# shieldv1_0.net
KiCad netlist of a schematic drawn in EAGLE
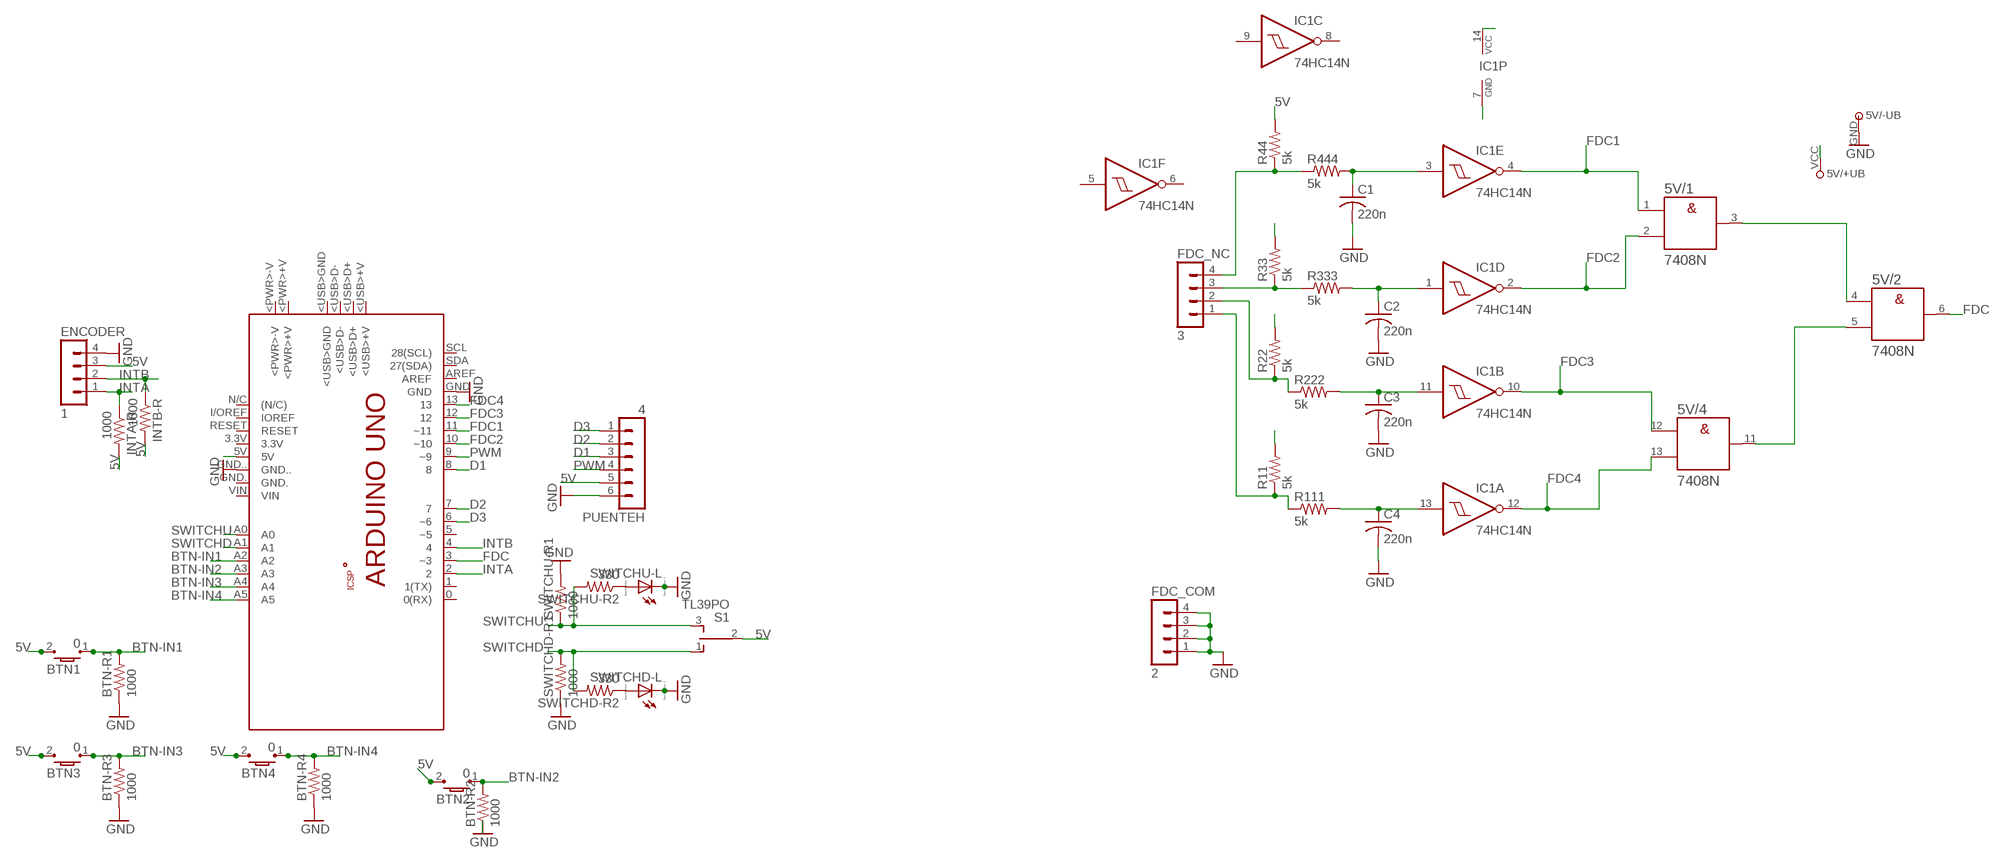
[diagram p0: schematic, sheet 1]

(export (version "E")
  (design (tool "Eeschema 10.0.6"))
  (components
    (comp (ref "5V")
      (value "7408N")
      (footprint "eagle-import:DIL14")
      (libsource (lib "eagle-import") (part "7408N"))
    )
    (comp (ref "BTN-R1")
      (value "1000")
      (footprint "eagle-import:0204_7")
      (libsource (lib "eagle-import") (part "resistor_R-US_0204/7"))
    )
    (comp (ref "BTN-R2")
      (value "1000")
      (footprint "eagle-import:0204_7")
      (libsource (lib "eagle-import") (part "resistor_R-US_0204/7"))
    )
    (comp (ref "BTN-R3")
      (value "1000")
      (footprint "eagle-import:0204_7")
      (libsource (lib "eagle-import") (part "resistor_R-US_0204/7"))
    )
    (comp (ref "BTN-R4")
      (value "1000")
      (footprint "eagle-import:0204_7")
      (libsource (lib "eagle-import") (part "resistor_R-US_0204/7"))
    )
    (comp (ref "BTN1")
      (value "0")
      (footprint "eagle-import:TL3303_J")
      (libsource (lib "eagle-import") (part "TL3302-J"))
    )
    (comp (ref "BTN2")
      (value "0")
      (footprint "eagle-import:TL3303_J")
      (libsource (lib "eagle-import") (part "TL3302-J"))
    )
    (comp (ref "BTN3")
      (value "0")
      (footprint "eagle-import:TL3303_J")
      (libsource (lib "eagle-import") (part "TL3302-J"))
    )
    (comp (ref "BTN4")
      (value "0")
      (footprint "eagle-import:TL3303_J")
      (libsource (lib "eagle-import") (part "TL3302-J"))
    )
    (comp (ref "C1")
      (value "220n")
      (footprint "eagle-import:C025-030X050")
      (libsource (lib "eagle-import") (part "C-US025-030X050"))
    )
    (comp (ref "C2")
      (value "220n")
      (footprint "eagle-import:C025-030X050")
      (libsource (lib "eagle-import") (part "C-US025-030X050"))
    )
    (comp (ref "C3")
      (value "220n")
      (footprint "eagle-import:C025-030X050")
      (libsource (lib "eagle-import") (part "C-US025-030X050"))
    )
    (comp (ref "C4")
      (value "220n")
      (footprint "eagle-import:C025-030X050")
      (libsource (lib "eagle-import") (part "C-US025-030X050"))
    )
    (comp (ref "ENCODER")
      (value "1")
      (footprint "eagle-import:MA04-1")
      (libsource (lib "eagle-import") (part "MA04-1"))
    )
    (comp (ref "FDC_COM")
      (value "2")
      (footprint "eagle-import:MA04-1")
      (libsource (lib "eagle-import") (part "MA04-1"))
    )
    (comp (ref "FDC_NC")
      (value "3")
      (footprint "eagle-import:MA04-1")
      (libsource (lib "eagle-import") (part "MA04-1"))
    )
    (comp (ref "IC1")
      (value "74HC14N")
      (footprint "eagle-import:DIL14")
      (libsource (lib "eagle-import") (part "7414NHC"))
    )
    (comp (ref "INTA-R")
      (value "1000")
      (footprint "eagle-import:0204_7")
      (libsource (lib "eagle-import") (part "resistor_R-US_0204/7"))
    )
    (comp (ref "INTB-R")
      (value "1000")
      (footprint "eagle-import:0204_7")
      (libsource (lib "eagle-import") (part "resistor_R-US_0204/7"))
    )
    (comp (ref "PCB1")
      (value "ARDUINO_UNO")
      (footprint "eagle-import:ARDUINO_UNO")
      (libsource (lib "eagle-import") (part "ARDUINO_UNO"))
    )
    (comp (ref "PUENTEH")
      (value "4")
      (footprint "eagle-import:MA06-1")
      (libsource (lib "eagle-import") (part "MA06-1"))
    )
    (comp (ref "R11")
      (value "5k")
      (footprint "eagle-import:0204_7")
      (libsource (lib "eagle-import") (part "R-US_0204/7"))
    )
    (comp (ref "R22")
      (value "5k")
      (footprint "eagle-import:0204_7")
      (libsource (lib "eagle-import") (part "R-US_0204/7"))
    )
    (comp (ref "R33")
      (value "5k")
      (footprint "eagle-import:0204_7")
      (libsource (lib "eagle-import") (part "R-US_0204/7"))
    )
    (comp (ref "R44")
      (value "5k")
      (footprint "eagle-import:0204_7")
      (libsource (lib "eagle-import") (part "R-US_0204/7"))
    )
    (comp (ref "R111")
      (value "5k")
      (footprint "eagle-import:0204_7")
      (libsource (lib "eagle-import") (part "R-US_0204/7"))
    )
    (comp (ref "R222")
      (value "5k")
      (footprint "eagle-import:0204_7")
      (libsource (lib "eagle-import") (part "R-US_0204/7"))
    )
    (comp (ref "R333")
      (value "5k")
      (footprint "eagle-import:0204_7")
      (libsource (lib "eagle-import") (part "R-US_0204/7"))
    )
    (comp (ref "R444")
      (value "5k")
      (footprint "eagle-import:0204_7")
      (libsource (lib "eagle-import") (part "R-US_0204/7"))
    )
    (comp (ref "S1")
      (value "TL39PO")
      (footprint "eagle-import:TL3XPO")
      (libsource (lib "eagle-import") (part "TL39PO"))
    )
    (comp (ref "SWITCHD-L")
      (value "LED_ELD260")
      (footprint "eagle-import:LED_LD260")
      (libsource (lib "eagle-import") (part "LED_ELD260"))
    )
    (comp (ref "SWITCHD-R1")
      (value "1000")
      (footprint "eagle-import:0204_7")
      (libsource (lib "eagle-import") (part "resistor_R-US_0204/7"))
    )
    (comp (ref "SWITCHD-R2")
      (value "330")
      (footprint "eagle-import:0204_7")
      (libsource (lib "eagle-import") (part "resistor_R-US_0204/7"))
    )
    (comp (ref "SWITCHU-L")
      (value "LED_ELD260")
      (footprint "eagle-import:LED_LD260")
      (libsource (lib "eagle-import") (part "LED_ELD260"))
    )
    (comp (ref "SWITCHU-R1")
      (value "1000")
      (footprint "eagle-import:0204_7")
      (libsource (lib "eagle-import") (part "resistor_R-US_0204/7"))
    )
    (comp (ref "SWITCHU-R2")
      (value "330")
      (footprint "eagle-import:0204_7")
      (libsource (lib "eagle-import") (part "resistor_R-US_0204/7"))
    )
  )
  (nets
    (net (code "1") (name "/5V") (class "Default")
      (node (ref "5V") (pin "VCC") (pinfunction "+UB_VCC") (pintype "power_in"))
      (node (ref "BTN1") (pin "2") (pinfunction "2_2") (pintype "passive"))
      (node (ref "BTN2") (pin "2") (pinfunction "2_2") (pintype "passive"))
      (node (ref "BTN3") (pin "2") (pinfunction "2_2") (pintype "passive"))
      (node (ref "BTN4") (pin "2") (pinfunction "2_2") (pintype "passive"))
      (node (ref "ENCODER") (pin "3") (pinfunction "3_3") (pintype "passive"))
      (node (ref "IC1") (pin "14") (pinfunction "VCC_14") (pintype "power_in"))
      (node (ref "INTA-R") (pin "2") (pinfunction "2_2") (pintype "passive"))
      (node (ref "INTB-R") (pin "2") (pinfunction "2_2") (pintype "passive"))
      (node (ref "PCB1") (pin "5V") (pinfunction "5V_5V") (pintype "bidirectional"))
      (node (ref "PUENTEH") (pin "5") (pinfunction "5_5") (pintype "passive"))
      (node (ref "R11") (pin "2") (pinfunction "2_2") (pintype "passive"))
      (node (ref "R22") (pin "2") (pinfunction "2_2") (pintype "passive"))
      (node (ref "R33") (pin "2") (pinfunction "2_2") (pintype "passive"))
      (node (ref "R44") (pin "2") (pinfunction "2_2") (pintype "passive"))
      (node (ref "S1") (pin "2") (pinfunction "P_2") (pintype "passive"))
    )
    (net (code "2") (name "/BTN-IN1") (class "Default")
      (node (ref "BTN-R1") (pin "2") (pinfunction "2_2") (pintype "passive"))
      (node (ref "BTN1") (pin "1") (pinfunction "1_1") (pintype "passive"))
      (node (ref "PCB1") (pin "A2") (pinfunction "A2_A2") (pintype "bidirectional"))
    )
    (net (code "3") (name "/BTN-IN2") (class "Default")
      (node (ref "BTN-R2") (pin "2") (pinfunction "2_2") (pintype "passive"))
      (node (ref "BTN2") (pin "1") (pinfunction "1_1") (pintype "passive"))
      (node (ref "PCB1") (pin "A3") (pinfunction "A3_A3") (pintype "bidirectional"))
    )
    (net (code "4") (name "/BTN-IN3") (class "Default")
      (node (ref "BTN-R3") (pin "2") (pinfunction "2_2") (pintype "passive"))
      (node (ref "BTN3") (pin "1") (pinfunction "1_1") (pintype "passive"))
      (node (ref "PCB1") (pin "A4") (pinfunction "A4_A4") (pintype "bidirectional"))
    )
    (net (code "5") (name "/BTN-IN4") (class "Default")
      (node (ref "BTN-R4") (pin "2") (pinfunction "2_2") (pintype "passive"))
      (node (ref "BTN4") (pin "1") (pinfunction "1_1") (pintype "passive"))
      (node (ref "PCB1") (pin "A5") (pinfunction "A5_A5") (pintype "bidirectional"))
    )
    (net (code "6") (name "/D1") (class "Default")
      (node (ref "PCB1") (pin "8") (pinfunction "8_8") (pintype "bidirectional"))
      (node (ref "PUENTEH") (pin "3") (pinfunction "3_3") (pintype "passive"))
    )
    (net (code "7") (name "/D2") (class "Default")
      (node (ref "PCB1") (pin "7") (pinfunction "7_7") (pintype "bidirectional"))
      (node (ref "PUENTEH") (pin "2") (pinfunction "2_2") (pintype "passive"))
    )
    (net (code "8") (name "/D3") (class "Default")
      (node (ref "PCB1") (pin "6") (pinfunction "~{6}_6") (pintype "bidirectional"))
      (node (ref "PUENTEH") (pin "1") (pinfunction "1_1") (pintype "passive"))
    )
    (net (code "9") (name "/FDC") (class "Default")
      (node (ref "5V") (pin "6") (pinfunction "Y_6") (pintype "output"))
      (node (ref "PCB1") (pin "3") (pinfunction "~{3}_3") (pintype "bidirectional"))
    )
    (net (code "10") (name "/FDC1") (class "Default")
      (node (ref "5V") (pin "1") (pinfunction "A_1") (pintype "input"))
      (node (ref "IC1") (pin "4") (pinfunction "O_4") (pintype "output"))
      (node (ref "PCB1") (pin "11") (pinfunction "~{11}_11") (pintype "bidirectional"))
    )
    (net (code "11") (name "/FDC2") (class "Default")
      (node (ref "5V") (pin "2") (pinfunction "B_2") (pintype "input"))
      (node (ref "IC1") (pin "2") (pinfunction "O_2") (pintype "output"))
      (node (ref "PCB1") (pin "10") (pinfunction "~{10}_10") (pintype "bidirectional"))
    )
    (net (code "12") (name "/FDC3") (class "Default")
      (node (ref "5V") (pin "12") (pinfunction "A_12") (pintype "input"))
      (node (ref "IC1") (pin "10") (pinfunction "O_10") (pintype "output"))
      (node (ref "PCB1") (pin "12") (pinfunction "12_12") (pintype "bidirectional"))
    )
    (net (code "13") (name "/FDC4") (class "Default")
      (node (ref "5V") (pin "13") (pinfunction "B_13") (pintype "input"))
      (node (ref "IC1") (pin "12") (pinfunction "O_12") (pintype "output"))
      (node (ref "PCB1") (pin "13") (pinfunction "13_13") (pintype "bidirectional"))
    )
    (net (code "14") (name "/INTA") (class "Default")
      (node (ref "ENCODER") (pin "1") (pinfunction "1_1") (pintype "passive"))
      (node (ref "INTA-R") (pin "1") (pinfunction "1_1") (pintype "passive"))
      (node (ref "PCB1") (pin "2") (pinfunction "2_2") (pintype "bidirectional"))
    )
    (net (code "15") (name "/INTB") (class "Default")
      (node (ref "ENCODER") (pin "2") (pinfunction "2_2") (pintype "passive"))
      (node (ref "INTB-R") (pin "1") (pinfunction "1_1") (pintype "passive"))
      (node (ref "PCB1") (pin "4") (pinfunction "4_4") (pintype "bidirectional"))
    )
    (net (code "16") (name "/PWM") (class "Default")
      (node (ref "PCB1") (pin "9") (pinfunction "~{9}_9") (pintype "bidirectional"))
      (node (ref "PUENTEH") (pin "4") (pinfunction "4_4") (pintype "passive"))
    )
    (net (code "17") (name "/SWITCHD") (class "Default")
      (node (ref "PCB1") (pin "A1") (pinfunction "A1_A1") (pintype "bidirectional"))
      (node (ref "S1") (pin "1") (pinfunction "O_1") (pintype "passive"))
      (node (ref "SWITCHD-R1") (pin "2") (pinfunction "2_2") (pintype "passive"))
      (node (ref "SWITCHD-R2") (pin "2") (pinfunction "2_2") (pintype "passive"))
    )
    (net (code "18") (name "/SWITCHU") (class "Default")
      (node (ref "PCB1") (pin "A0") (pinfunction "A0_A0") (pintype "bidirectional"))
      (node (ref "S1") (pin "3") (pinfunction "S_3") (pintype "passive"))
      (node (ref "SWITCHU-R1") (pin "1") (pinfunction "1_1") (pintype "passive"))
      (node (ref "SWITCHU-R2") (pin "2") (pinfunction "2_2") (pintype "passive"))
    )
    (net (code "19") (name "GND") (class "Default")
      (node (ref "5V") (pin "GND") (pinfunction "-UB_GND") (pintype "power_in"))
      (node (ref "BTN-R1") (pin "1") (pinfunction "1_1") (pintype "passive"))
      (node (ref "BTN-R2") (pin "1") (pinfunction "1_1") (pintype "passive"))
      (node (ref "BTN-R3") (pin "1") (pinfunction "1_1") (pintype "passive"))
      (node (ref "BTN-R4") (pin "1") (pinfunction "1_1") (pintype "passive"))
      (node (ref "C1") (pin "2") (pinfunction "2_2") (pintype "passive"))
      (node (ref "C2") (pin "2") (pinfunction "2_2") (pintype "passive"))
      (node (ref "C3") (pin "2") (pinfunction "2_2") (pintype "passive"))
      (node (ref "C4") (pin "2") (pinfunction "2_2") (pintype "passive"))
      (node (ref "ENCODER") (pin "4") (pinfunction "4_4") (pintype "passive"))
      (node (ref "FDC_COM") (pin "1") (pinfunction "1_1") (pintype "passive"))
      (node (ref "FDC_COM") (pin "2") (pinfunction "2_2") (pintype "passive"))
      (node (ref "FDC_COM") (pin "3") (pinfunction "3_3") (pintype "passive"))
      (node (ref "FDC_COM") (pin "4") (pinfunction "4_4") (pintype "passive"))
      (node (ref "IC1") (pin "7") (pinfunction "GND_7") (pintype "power_in"))
      (node (ref "PCB1") (pin "GND") (pinfunction "GND_GND") (pintype "bidirectional"))
      (node (ref "PCB1") (pin "GND..") (pinfunction "GND.._GND..") (pintype "bidirectional"))
      (node (ref "PUENTEH") (pin "6") (pinfunction "6_6") (pintype "passive"))
      (node (ref "SWITCHD-L") (pin "K") (pinfunction "C_K") (pintype "passive"))
      (node (ref "SWITCHD-R1") (pin "1") (pinfunction "1_1") (pintype "passive"))
      (node (ref "SWITCHU-L") (pin "K") (pinfunction "C_K") (pintype "passive"))
      (node (ref "SWITCHU-R1") (pin "2") (pinfunction "2_2") (pintype "passive"))
    )
    (net (code "20") (name "Net-(5VC-Y)") (class "Default")
      (node (ref "5V") (pin "3") (pinfunction "Y_3") (pintype "output"))
      (node (ref "5V") (pin "4") (pinfunction "A_4") (pintype "input"))
    )
    (net (code "21") (name "Net-(5VD-B)") (class "Default")
      (node (ref "5V") (pin "11") (pinfunction "Y_11") (pintype "output"))
      (node (ref "5V") (pin "5") (pinfunction "B_5") (pintype "input"))
    )
    (net (code "22") (name "Net-(FDC_NC-Pad1)") (class "Default")
      (node (ref "FDC_NC") (pin "1") (pinfunction "1_1") (pintype "passive"))
      (node (ref "R11") (pin "1") (pinfunction "1_1") (pintype "passive"))
      (node (ref "R111") (pin "1") (pinfunction "1_1") (pintype "passive"))
    )
    (net (code "23") (name "Net-(FDC_NC-Pad2)") (class "Default")
      (node (ref "FDC_NC") (pin "2") (pinfunction "2_2") (pintype "passive"))
      (node (ref "R22") (pin "1") (pinfunction "1_1") (pintype "passive"))
      (node (ref "R222") (pin "1") (pinfunction "1_1") (pintype "passive"))
    )
    (net (code "24") (name "Net-(FDC_NC-Pad3)") (class "Default")
      (node (ref "FDC_NC") (pin "3") (pinfunction "3_3") (pintype "passive"))
      (node (ref "R33") (pin "1") (pinfunction "1_1") (pintype "passive"))
      (node (ref "R333") (pin "1") (pinfunction "1_1") (pintype "passive"))
    )
    (net (code "25") (name "Net-(FDC_NC-Pad4)") (class "Default")
      (node (ref "FDC_NC") (pin "4") (pinfunction "4_4") (pintype "passive"))
      (node (ref "R44") (pin "1") (pinfunction "1_1") (pintype "passive"))
      (node (ref "R444") (pin "1") (pinfunction "1_1") (pintype "passive"))
    )
    (net (code "26") (name "Net-(IC1A-I)") (class "Default")
      (node (ref "C4") (pin "1") (pinfunction "1_1") (pintype "passive"))
      (node (ref "IC1") (pin "13") (pinfunction "I_13") (pintype "input"))
      (node (ref "R111") (pin "2") (pinfunction "2_2") (pintype "passive"))
    )
    (net (code "27") (name "Net-(IC1B-I)") (class "Default")
      (node (ref "C3") (pin "1") (pinfunction "1_1") (pintype "passive"))
      (node (ref "IC1") (pin "11") (pinfunction "I_11") (pintype "input"))
      (node (ref "R222") (pin "2") (pinfunction "2_2") (pintype "passive"))
    )
    (net (code "28") (name "Net-(IC1D-I)") (class "Default")
      (node (ref "C2") (pin "1") (pinfunction "1_1") (pintype "passive"))
      (node (ref "IC1") (pin "1") (pinfunction "I_1") (pintype "input"))
      (node (ref "R333") (pin "2") (pinfunction "2_2") (pintype "passive"))
    )
    (net (code "29") (name "Net-(IC1E-I)") (class "Default")
      (node (ref "C1") (pin "1") (pinfunction "1_1") (pintype "passive"))
      (node (ref "IC1") (pin "3") (pinfunction "I_3") (pintype "input"))
      (node (ref "R444") (pin "2") (pinfunction "2_2") (pintype "passive"))
    )
    (net (code "30") (name "Net-(SWITCHD-L-PadA)") (class "Default")
      (node (ref "SWITCHD-L") (pin "A") (pinfunction "A_A") (pintype "passive"))
      (node (ref "SWITCHD-R2") (pin "1") (pinfunction "1_1") (pintype "passive"))
    )
    (net (code "31") (name "Net-(SWITCHU-L-PadA)") (class "Default")
      (node (ref "SWITCHU-L") (pin "A") (pinfunction "A_A") (pintype "passive"))
      (node (ref "SWITCHU-R2") (pin "1") (pinfunction "1_1") (pintype "passive"))
    )
    (net (code "32") (name "unconnected-(IC1C-I-Pad9)") (class "Default")
      (node (ref "IC1") (pin "9") (pinfunction "I_9") (pintype "input"))
    )
    (net (code "33") (name "unconnected-(IC1C-O-Pad8)") (class "Default")
      (node (ref "IC1") (pin "8") (pinfunction "O_8") (pintype "output"))
    )
    (net (code "34") (name "unconnected-(IC1F-I-Pad5)") (class "Default")
      (node (ref "IC1") (pin "5") (pinfunction "I_5") (pintype "input"))
    )
    (net (code "35") (name "unconnected-(IC1F-O-Pad6)") (class "Default")
      (node (ref "IC1") (pin "6") (pinfunction "O_6") (pintype "output"))
    )
    (net (code "36") (name "unconnected-(PCB1-(N{slash}C)-PadN{slash}C)") (class "Default")
      (node (ref "PCB1") (pin "N/C") (pinfunction "(N/C)_N/C") (pintype "bidirectional"))
    )
    (net (code "37") (name "unconnected-(PCB1-0(RX)-Pad0)") (class "Default")
      (node (ref "PCB1") (pin "0") (pinfunction "0(RX)_0") (pintype "bidirectional"))
    )
    (net (code "38") (name "unconnected-(PCB1-1(TX)-Pad1)") (class "Default")
      (node (ref "PCB1") (pin "1") (pinfunction "1(TX)_1") (pintype "bidirectional"))
    )
    (net (code "39") (name "unconnected-(PCB1-27(SDA)-PadSDA)") (class "Default")
      (node (ref "PCB1") (pin "SDA") (pinfunction "27(SDA)_SDA") (pintype "bidirectional"))
    )
    (net (code "40") (name "unconnected-(PCB1-28(SCL)-PadSCL)") (class "Default")
      (node (ref "PCB1") (pin "SCL") (pinfunction "28(SCL)_SCL") (pintype "bidirectional"))
    )
    (net (code "41") (name "unconnected-(PCB1-IOREF-PadI{slash}OREF)") (class "Default")
      (node (ref "PCB1") (pin "I/OREF") (pinfunction "IOREF_I/OREF") (pintype "bidirectional"))
    )
    (net (code "42") (name "unconnected-(PCB1-Pad+5V)") (class "Default")
      (node (ref "PCB1") (pin "+5V") (pinfunction "+5V_+5V") (pintype "bidirectional"))
    )
    (net (code "43") (name "unconnected-(PCB1-Pad3.3V)") (class "Default")
      (node (ref "PCB1") (pin "3.3V") (pinfunction "3.3V_3.3V") (pintype "bidirectional"))
    )
    (net (code "44") (name "unconnected-(PCB1-Pad<PWR>+V)") (class "Default")
      (node (ref "PCB1") (pin "<PWR>+V") (pinfunction "<PWR>+V_<PWR>+V") (pintype "bidirectional"))
    )
    (net (code "45") (name "unconnected-(PCB1-Pad<PWR>-V)") (class "Default")
      (node (ref "PCB1") (pin "<PWR>-V") (pinfunction "<PWR>-V_<PWR>-V") (pintype "bidirectional"))
    )
    (net (code "46") (name "unconnected-(PCB1-Pad<USB>+V)") (class "Default")
      (node (ref "PCB1") (pin "<USB>+V") (pinfunction "<USB>+V_<USB>+V") (pintype "bidirectional"))
    )
    (net (code "47") (name "unconnected-(PCB1-Pad<USB>D+)") (class "Default")
      (node (ref "PCB1") (pin "<USB>D+") (pinfunction "<USB>D+_<USB>D+") (pintype "bidirectional"))
    )
    (net (code "48") (name "unconnected-(PCB1-Pad<USB>D-)") (class "Default")
      (node (ref "PCB1") (pin "<USB>D-") (pinfunction "<USB>D-_<USB>D-") (pintype "bidirectional"))
    )
    (net (code "49") (name "unconnected-(PCB1-Pad<USB>GND)") (class "Default")
      (node (ref "PCB1") (pin "<USB>GND") (pinfunction "<USB>GND_<USB>GND") (pintype "bidirectional"))
    )
    (net (code "50") (name "unconnected-(PCB1-PadAREF)") (class "Default")
      (node (ref "PCB1") (pin "AREF") (pinfunction "AREF_AREF") (pintype "bidirectional"))
    )
    (net (code "51") (name "unconnected-(PCB1-PadGND.)") (class "Default")
      (node (ref "PCB1") (pin "GND.") (pinfunction "GND._GND.") (pintype "bidirectional"))
    )
    (net (code "52") (name "unconnected-(PCB1-PadGND_)") (class "Default")
      (node (ref "PCB1") (pin "GND_") (pinfunction "GND__GND_") (pintype "bidirectional"))
    )
    (net (code "53") (name "unconnected-(PCB1-PadMISO)") (class "Default")
      (node (ref "PCB1") (pin "MISO") (pinfunction "MISO_MISO") (pintype "bidirectional"))
    )
    (net (code "54") (name "unconnected-(PCB1-PadMOSI)") (class "Default")
      (node (ref "PCB1") (pin "MOSI") (pinfunction "MOSI_MOSI") (pintype "bidirectional"))
    )
    (net (code "55") (name "unconnected-(PCB1-PadRESET)") (class "Default")
      (node (ref "PCB1") (pin "RESET") (pinfunction "RESET_RESET") (pintype "bidirectional"))
    )
    (net (code "56") (name "unconnected-(PCB1-PadRESET.)") (class "Default")
      (node (ref "PCB1") (pin "RESET.") (pinfunction "RESET._RESET.") (pintype "bidirectional"))
    )
    (net (code "57") (name "unconnected-(PCB1-PadSCK)") (class "Default")
      (node (ref "PCB1") (pin "SCK") (pinfunction "SCK_SCK") (pintype "bidirectional"))
    )
    (net (code "58") (name "unconnected-(PCB1-PadVIN)") (class "Default")
      (node (ref "PCB1") (pin "VIN") (pinfunction "VIN_VIN") (pintype "bidirectional"))
    )
    (net (code "59") (name "unconnected-(PCB1-~{5}-Pad5)") (class "Default")
      (node (ref "PCB1") (pin "5") (pinfunction "~{5}_5") (pintype "bidirectional"))
    )
  )
)
